# IdcProbe.net
KiCad netlist of a schematic drawn in EAGLE
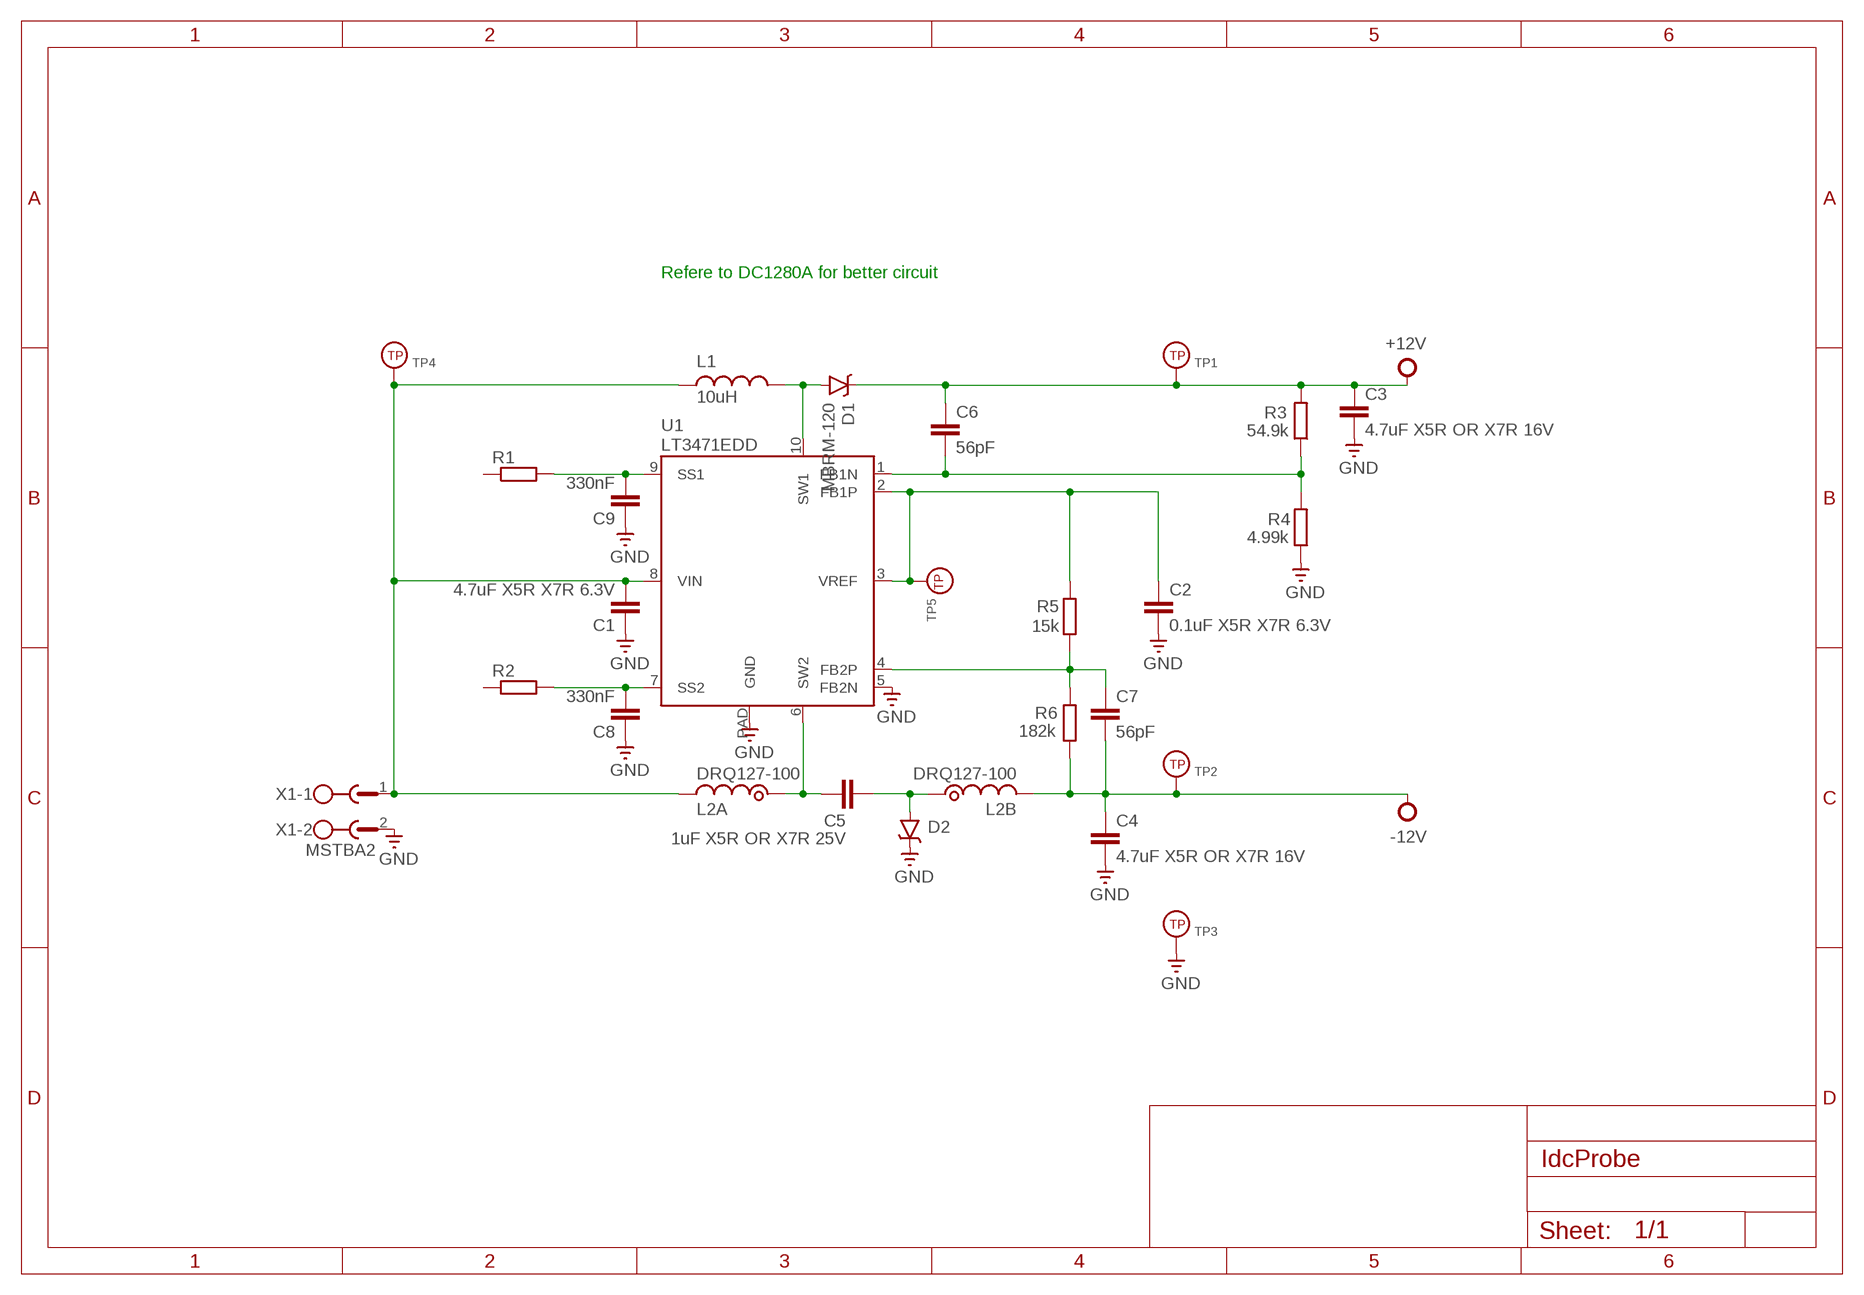
[diagram p0: schematic, sheet 1]

(export (version "E")
  (design (tool "Eeschema 10.0.6"))
  (components
    (comp (ref "C1")
      (value "4.7uF X5R X7R 6.3V")
      (footprint "eagle-import:C0603")
      (libsource (lib "eagle-import") (part "C-EUC0603"))
    )
    (comp (ref "C2")
      (value "0.1uF X5R X7R 6.3V")
      (footprint "eagle-import:C0603")
      (libsource (lib "eagle-import") (part "C-EUC0603"))
    )
    (comp (ref "C3")
      (value "4.7uF X5R OR X7R 16V")
      (footprint "eagle-import:C0603")
      (libsource (lib "eagle-import") (part "C-EUC0603"))
    )
    (comp (ref "C4")
      (value "4.7uF X5R OR X7R 16V")
      (footprint "eagle-import:C0603")
      (libsource (lib "eagle-import") (part "C-EUC0603"))
    )
    (comp (ref "C5")
      (value "1uF X5R OR X7R 25V")
      (footprint "eagle-import:C0603")
      (libsource (lib "eagle-import") (part "C-EUC0603"))
    )
    (comp (ref "C6")
      (value "56pF")
      (footprint "eagle-import:C0603")
      (libsource (lib "eagle-import") (part "C-EUC0603"))
    )
    (comp (ref "C7")
      (value "56pF")
      (footprint "eagle-import:C0603")
      (libsource (lib "eagle-import") (part "C-EUC0603"))
    )
    (comp (ref "C8")
      (value "330nF")
      (footprint "eagle-import:C0603")
      (libsource (lib "eagle-import") (part "C-EUC0603"))
    )
    (comp (ref "C9")
      (value "330nF")
      (footprint "eagle-import:C0603")
      (libsource (lib "eagle-import") (part "C-EUC0603"))
    )
    (comp (ref "D1")
      (value "MBRM-120")
      (footprint "eagle-import:POWERMITE1")
      (libsource (lib "eagle-import") (part "DIODE-SCHOTTKY"))
    )
    (comp (ref "D2")
      (value "MBRM-120")
      (footprint "eagle-import:POWERMITE1")
      (libsource (lib "eagle-import") (part "DIODE-SCHOTTKY"))
    )
    (comp (ref "L1")
      (value "10uH")
      (footprint "eagle-import:242408FPS")
      (fields (field (name "MPN") "242408FPS‑220M‑01 "))
      (libsource (lib "eagle-import") (part "INDUCTOR"))
    )
    (comp (ref "L2")
      (value "DRQ127-100")
      (footprint "eagle-import:DRQ127")
      (libsource (lib "eagle-import") (part "TRANSFORMER_DRQ127"))
    )
    (comp (ref "R1")
      (value "R-EU_R0603")
      (footprint "eagle-import:R0603")
      (libsource (lib "eagle-import") (part "R-EU_R0603"))
    )
    (comp (ref "R2")
      (value "R-EU_R0603")
      (footprint "eagle-import:R0603")
      (libsource (lib "eagle-import") (part "R-EU_R0603"))
    )
    (comp (ref "R3")
      (value "54.9k")
      (footprint "eagle-import:R0603")
      (libsource (lib "eagle-import") (part "R-EU_R0603"))
    )
    (comp (ref "R4")
      (value "4.99k")
      (footprint "eagle-import:R0603")
      (libsource (lib "eagle-import") (part "R-EU_R0603"))
    )
    (comp (ref "R5")
      (value "15k")
      (footprint "eagle-import:R0603")
      (libsource (lib "eagle-import") (part "R-EU_R0603"))
    )
    (comp (ref "R6")
      (value "182k")
      (footprint "eagle-import:R0603")
      (libsource (lib "eagle-import") (part "R-EU_R0603"))
    )
    (comp (ref "TP1")
      (value "TESTPOINT")
      (footprint "eagle-import:TESTHOOK")
      (libsource (lib "eagle-import") (part "TESTPOINT"))
    )
    (comp (ref "TP2")
      (value "TESTPOINT")
      (footprint "eagle-import:TESTHOOK")
      (libsource (lib "eagle-import") (part "TESTPOINT"))
    )
    (comp (ref "TP3")
      (value "TESTPOINT")
      (footprint "eagle-import:TESTHOOK")
      (libsource (lib "eagle-import") (part "TESTPOINT"))
    )
    (comp (ref "TP4")
      (value "TESTPOINT")
      (footprint "eagle-import:TESTHOOK")
      (libsource (lib "eagle-import") (part "TESTPOINT"))
    )
    (comp (ref "TP5")
      (value "TESTPOINT")
      (footprint "eagle-import:TESTHOOK")
      (libsource (lib "eagle-import") (part "TESTPOINT"))
    )
    (comp (ref "U1")
      (value "LT3471EDD")
      (footprint "eagle-import:DFN10-3X3")
      (libsource (lib "eagle-import") (part "LT3471EDD"))
    )
    (comp (ref "X1")
      (value "MSTBA2")
      (footprint "eagle-import:MSTBA2")
      (fields (field (name "MF") "FARNELL") (field (name "MPN") "1757242"))
      (libsource (lib "eagle-import") (part "MSTBA2"))
    )
  )
  (nets
    (net (code "1") (name "+12V") (class "Default")
      (node (ref "C3") (pin "1") (pinfunction "1_1") (pintype "passive"))
      (node (ref "C6") (pin "1") (pinfunction "1_1") (pintype "passive"))
      (node (ref "D1") (pin "1") (pinfunction "C_1") (pintype "passive"))
      (node (ref "R3") (pin "2") (pinfunction "2_2") (pintype "passive"))
      (node (ref "TP1") (pin "TP") (pinfunction "P$1_TP") (pintype "bidirectional"))
    )
    (net (code "2") (name "-12V") (class "Default")
      (node (ref "C4") (pin "1") (pinfunction "1_1") (pintype "passive"))
      (node (ref "C7") (pin "2") (pinfunction "2_2") (pintype "passive"))
      (node (ref "L2") (pin "4") (pinfunction "2_4") (pintype "passive"))
      (node (ref "R6") (pin "1") (pinfunction "1_1") (pintype "passive"))
      (node (ref "TP2") (pin "TP") (pinfunction "P$1_TP") (pintype "bidirectional"))
    )
    (net (code "3") (name "GND") (class "Default")
      (node (ref "C1") (pin "1") (pinfunction "1_1") (pintype "passive"))
      (node (ref "C2") (pin "2") (pinfunction "2_2") (pintype "passive"))
      (node (ref "C3") (pin "2") (pinfunction "2_2") (pintype "passive"))
      (node (ref "C4") (pin "2") (pinfunction "2_2") (pintype "passive"))
      (node (ref "C8") (pin "1") (pinfunction "1_1") (pintype "passive"))
      (node (ref "C9") (pin "1") (pinfunction "1_1") (pintype "passive"))
      (node (ref "D2") (pin "1") (pinfunction "C_1") (pintype "passive"))
      (node (ref "R4") (pin "1") (pinfunction "1_1") (pintype "passive"))
      (node (ref "TP3") (pin "TP") (pinfunction "P$1_TP") (pintype "bidirectional"))
      (node (ref "U1") (pin "5") (pinfunction "FB2N_5") (pintype "bidirectional"))
      (node (ref "U1") (pin "PAD") (pinfunction "GND_PAD") (pintype "bidirectional"))
      (node (ref "X1") (pin "2") (pinfunction "1_2") (pintype "passive"))
    )
    (net (code "4") (name "Net-(D1-A)") (class "Default")
      (node (ref "D1") (pin "2") (pinfunction "A_2") (pintype "passive"))
      (node (ref "L1") (pin "2") (pinfunction "2_2") (pintype "passive"))
      (node (ref "U1") (pin "10") (pinfunction "SW1_10") (pintype "bidirectional"))
    )
    (net (code "5") (name "Net-(D2-A)") (class "Default")
      (node (ref "C5") (pin "1") (pinfunction "1_1") (pintype "passive"))
      (node (ref "D2") (pin "2") (pinfunction "A_2") (pintype "passive"))
      (node (ref "L2") (pin "2") (pinfunction "1_2") (pintype "passive"))
    )
    (net (code "6") (name "Net-(L2A-2)") (class "Default")
      (node (ref "C1") (pin "2") (pinfunction "2_2") (pintype "passive"))
      (node (ref "L1") (pin "1") (pinfunction "1_1") (pintype "passive"))
      (node (ref "L2") (pin "3") (pinfunction "2_3") (pintype "passive"))
      (node (ref "TP4") (pin "TP") (pinfunction "P$1_TP") (pintype "bidirectional"))
      (node (ref "U1") (pin "8") (pinfunction "VIN_8") (pintype "bidirectional"))
      (node (ref "X1") (pin "1") (pinfunction "1_1") (pintype "passive"))
    )
    (net (code "7") (name "Net-(TP5-P$1)") (class "Default")
      (node (ref "C2") (pin "1") (pinfunction "1_1") (pintype "passive"))
      (node (ref "R5") (pin "1") (pinfunction "1_1") (pintype "passive"))
      (node (ref "TP5") (pin "TP") (pinfunction "P$1_TP") (pintype "bidirectional"))
      (node (ref "U1") (pin "2") (pinfunction "FB1P_2") (pintype "bidirectional"))
      (node (ref "U1") (pin "3") (pinfunction "VREF_3") (pintype "bidirectional"))
    )
    (net (code "8") (name "Net-(U1-FB1N)") (class "Default")
      (node (ref "C6") (pin "2") (pinfunction "2_2") (pintype "passive"))
      (node (ref "R3") (pin "1") (pinfunction "1_1") (pintype "passive"))
      (node (ref "R4") (pin "2") (pinfunction "2_2") (pintype "passive"))
      (node (ref "U1") (pin "1") (pinfunction "FB1N_1") (pintype "bidirectional"))
    )
    (net (code "9") (name "Net-(U1-FB2P)") (class "Default")
      (node (ref "C7") (pin "1") (pinfunction "1_1") (pintype "passive"))
      (node (ref "R5") (pin "2") (pinfunction "2_2") (pintype "passive"))
      (node (ref "R6") (pin "2") (pinfunction "2_2") (pintype "passive"))
      (node (ref "U1") (pin "4") (pinfunction "FB2P_4") (pintype "bidirectional"))
    )
    (net (code "10") (name "Net-(U1-SS1)") (class "Default")
      (node (ref "C9") (pin "2") (pinfunction "2_2") (pintype "passive"))
      (node (ref "R1") (pin "2") (pinfunction "2_2") (pintype "passive"))
      (node (ref "U1") (pin "9") (pinfunction "SS1_9") (pintype "bidirectional"))
    )
    (net (code "11") (name "Net-(U1-SS2)") (class "Default")
      (node (ref "C8") (pin "2") (pinfunction "2_2") (pintype "passive"))
      (node (ref "R2") (pin "2") (pinfunction "2_2") (pintype "passive"))
      (node (ref "U1") (pin "7") (pinfunction "SS2_7") (pintype "bidirectional"))
    )
    (net (code "12") (name "Net-(U1-SW2)") (class "Default")
      (node (ref "C5") (pin "2") (pinfunction "2_2") (pintype "passive"))
      (node (ref "L2") (pin "1") (pinfunction "1_1") (pintype "passive"))
      (node (ref "U1") (pin "6") (pinfunction "SW2_6") (pintype "bidirectional"))
    )
    (net (code "13") (name "unconnected-(R1-Pad1)") (class "Default")
      (node (ref "R1") (pin "1") (pinfunction "1_1") (pintype "passive"))
    )
    (net (code "14") (name "unconnected-(R2-Pad1)") (class "Default")
      (node (ref "R2") (pin "1") (pinfunction "1_1") (pintype "passive"))
    )
  )
)
